# RCA.net
KiCad netlist of a schematic drawn in EAGLE
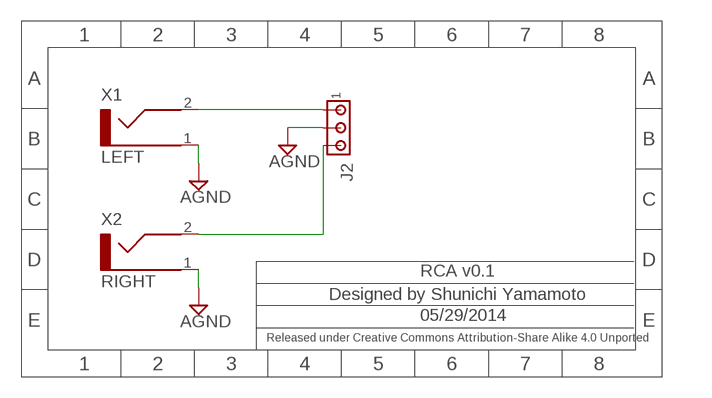
[diagram p0: schematic, sheet 1]

(export (version "E")
  (design (tool "Eeschema 10.0.6"))
  (components
    (comp (ref "J2")
      (value "MTA03-100")
      (footprint "eagle-import:10X03MTA")
      (libsource (lib "eagle-import") (part "MTA03-100"))
    )
    (comp (ref "X1")
      (value "LEFT")
      (footprint "eagle-import:RCA_JACK_CUI")
      (libsource (lib "eagle-import") (part "RCA_JACK_CUI"))
    )
    (comp (ref "X2")
      (value "RIGHT")
      (footprint "eagle-import:RCA_JACK_CUI")
      (libsource (lib "eagle-import") (part "RCA_JACK_CUI"))
    )
  )
  (nets
    (net (code "1") (name "AGND") (class "Default")
      (node (ref "J2") (pin "2") (pinfunction "2_2") (pintype "passive"))
      (node (ref "X1") (pin "1") (pinfunction "1_1") (pintype "bidirectional"))
      (node (ref "X2") (pin "1") (pinfunction "1_1") (pintype "bidirectional"))
    )
    (net (code "2") (name "Net-(J2-Pad1)") (class "Default")
      (node (ref "J2") (pin "1") (pinfunction "1_1") (pintype "passive"))
      (node (ref "X1") (pin "2") (pinfunction "2_2") (pintype "bidirectional"))
    )
    (net (code "3") (name "Net-(J2-Pad3)") (class "Default")
      (node (ref "J2") (pin "3") (pinfunction "3_3") (pintype "passive"))
      (node (ref "X2") (pin "2") (pinfunction "2_2") (pintype "bidirectional"))
    )
  )
)
